# FX2LP.net
KiCad netlist of a schematic drawn in Altium Designer
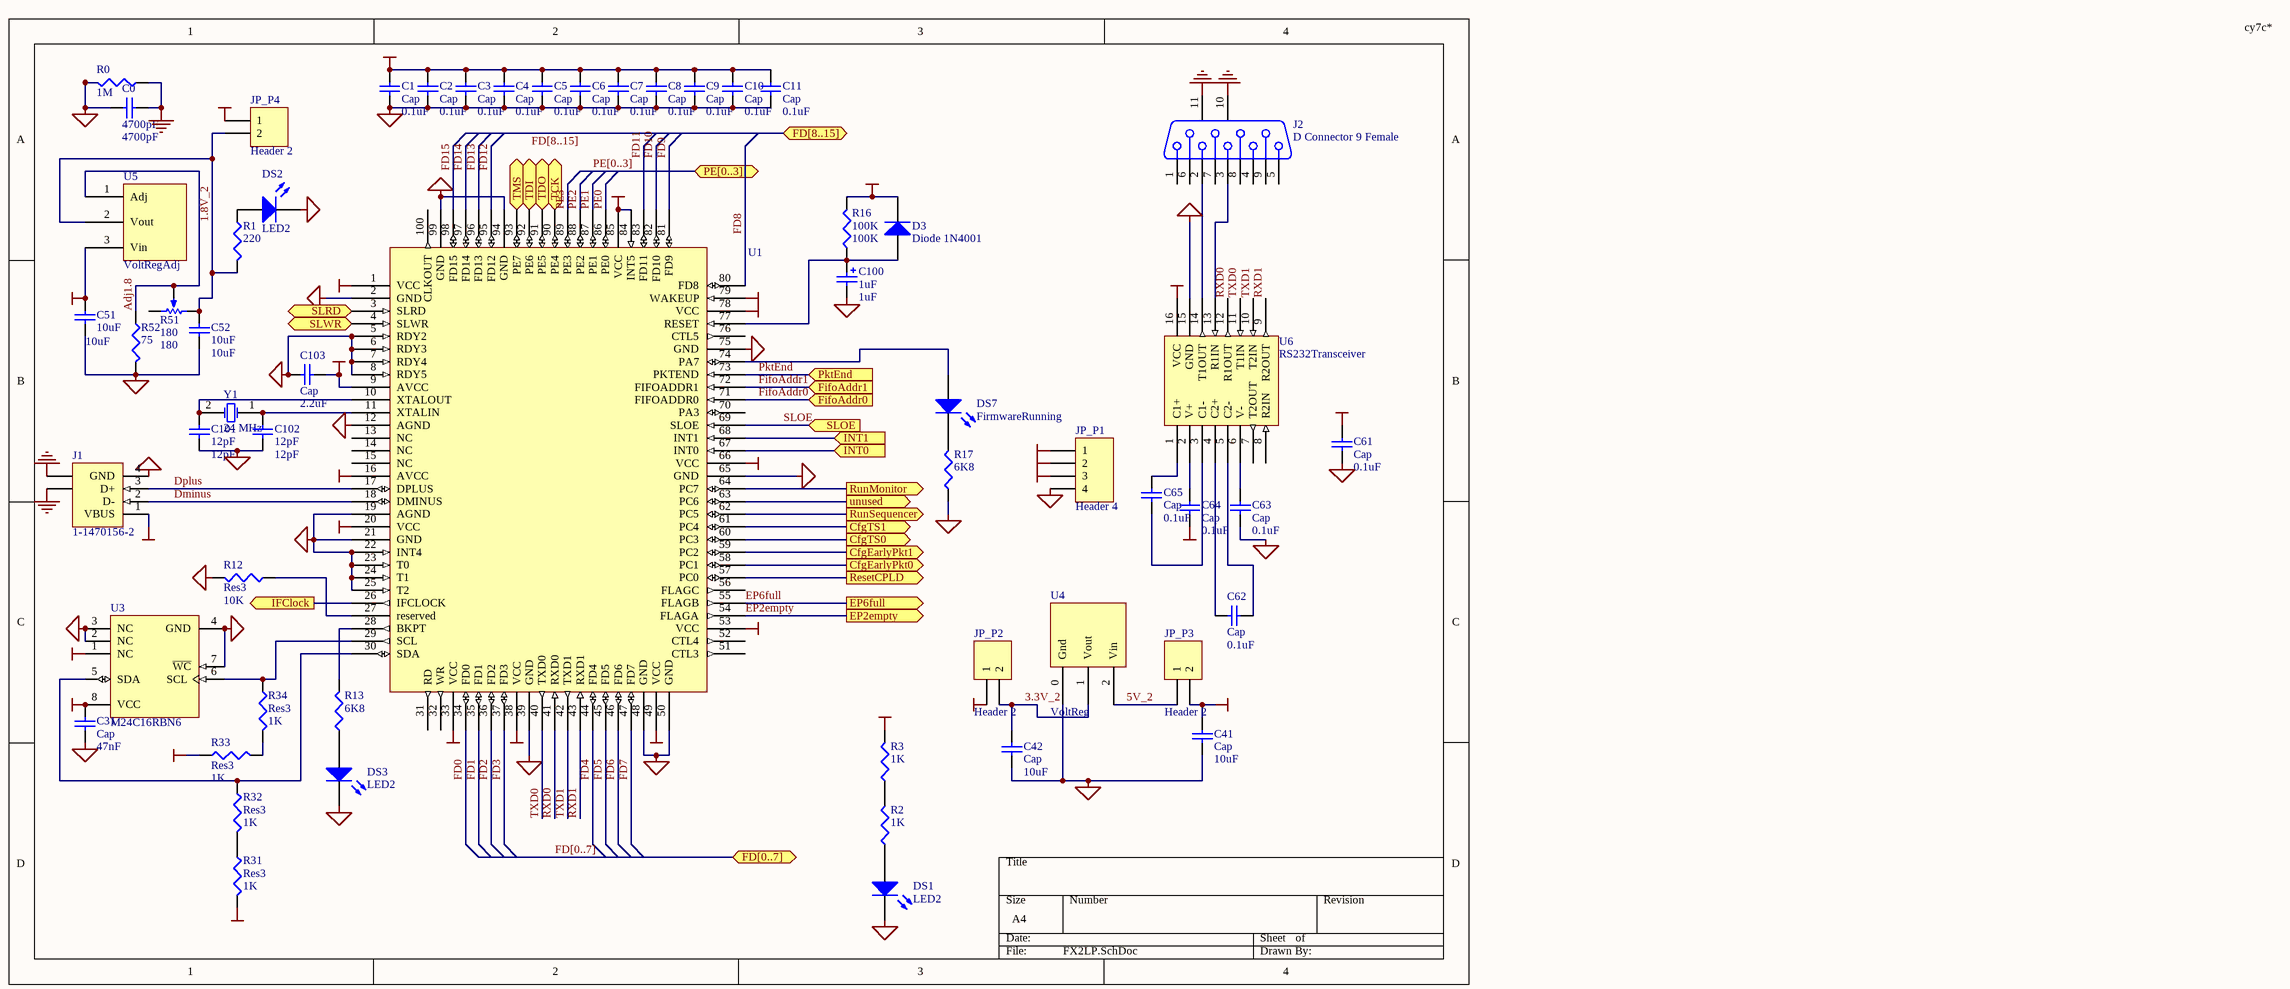
[diagram p0: FX2LP.SchDoc]

(export (version "E")
  (design (tool "Eeschema 10.0.6"))
  (components
    (comp (ref "C0")
      (value "4700pF")
      (footprint "CAP 10")
      (description "Capacitor")
      (fields (field (name "ALTIUM_VALUE") "4700pF") (field (name "PUBLISHER") "Altium Limited"))
      (libsource (lib "Miscellaneous Devices") (part "Cap"))
    )
    (comp (ref "C1")
      (value "Cap")
      (footprint "CAP 10")
      (description "Capacitor")
      (fields (field (name "ALTIUM_VALUE") "0.1uF") (field (name "PUBLISHER") "Altium Limited"))
      (libsource (lib "Miscellaneous Devices") (part "Cap"))
    )
    (comp (ref "C2")
      (value "Cap")
      (footprint "CAP 10")
      (description "Capacitor")
      (fields (field (name "ALTIUM_VALUE") "0.1uF") (field (name "PUBLISHER") "Altium Limited"))
      (libsource (lib "Miscellaneous Devices") (part "Cap"))
    )
    (comp (ref "C3")
      (value "Cap")
      (footprint "CAP 10")
      (description "Capacitor")
      (fields (field (name "ALTIUM_VALUE") "0.1uF") (field (name "PUBLISHER") "Altium Limited"))
      (libsource (lib "Miscellaneous Devices") (part "Cap"))
    )
    (comp (ref "C4")
      (value "Cap")
      (footprint "CAP 10")
      (description "Capacitor")
      (fields (field (name "ALTIUM_VALUE") "0.1uF") (field (name "PUBLISHER") "Altium Limited"))
      (libsource (lib "Miscellaneous Devices") (part "Cap"))
    )
    (comp (ref "C5")
      (value "Cap")
      (footprint "CAP 10")
      (description "Capacitor")
      (fields (field (name "ALTIUM_VALUE") "0.1uF") (field (name "PUBLISHER") "Altium Limited"))
      (libsource (lib "Miscellaneous Devices") (part "Cap"))
    )
    (comp (ref "C6")
      (value "Cap")
      (footprint "CAP 10")
      (description "Capacitor")
      (fields (field (name "ALTIUM_VALUE") "0.1uF") (field (name "PUBLISHER") "Altium Limited"))
      (libsource (lib "Miscellaneous Devices") (part "Cap"))
    )
    (comp (ref "C7")
      (value "Cap")
      (footprint "CAP 10")
      (description "Capacitor")
      (fields (field (name "ALTIUM_VALUE") "0.1uF") (field (name "PUBLISHER") "Altium Limited"))
      (libsource (lib "Miscellaneous Devices") (part "Cap"))
    )
    (comp (ref "C8")
      (value "Cap")
      (footprint "CAP 10")
      (description "Capacitor")
      (fields (field (name "ALTIUM_VALUE") "0.1uF") (field (name "PUBLISHER") "Altium Limited"))
      (libsource (lib "Miscellaneous Devices") (part "Cap"))
    )
    (comp (ref "C9")
      (value "Cap")
      (footprint "CAP 10")
      (description "Capacitor")
      (fields (field (name "ALTIUM_VALUE") "0.1uF") (field (name "PUBLISHER") "Altium Limited"))
      (libsource (lib "Miscellaneous Devices") (part "Cap"))
    )
    (comp (ref "C10")
      (value "Cap")
      (footprint "CAP 10")
      (description "Capacitor")
      (fields (field (name "ALTIUM_VALUE") "0.1uF") (field (name "PUBLISHER") "Altium Limited"))
      (libsource (lib "Miscellaneous Devices") (part "Cap"))
    )
    (comp (ref "C11")
      (value "Cap")
      (footprint "CAP 10")
      (description "Capacitor")
      (fields (field (name "ALTIUM_VALUE") "0.1uF") (field (name "PUBLISHER") "Altium Limited"))
      (libsource (lib "Miscellaneous Devices") (part "Cap"))
    )
    (comp (ref "C31")
      (value "Cap")
      (footprint "CAP 10")
      (description "Capacitor")
      (fields (field (name "ALTIUM_VALUE") "47nF") (field (name "PUBLISHER") "Altium Limited"))
      (libsource (lib "Miscellaneous Devices") (part "Cap"))
    )
    (comp (ref "C41")
      (value "Cap")
      (footprint "1206(2)")
      (description "Capacitor")
      (fields (field (name "ALTIUM_VALUE") "10uF") (field (name "PUBLISHER") "Altium Limited"))
      (libsource (lib "Miscellaneous Devices") (part "Cap"))
    )
    (comp (ref "C42")
      (value "Cap")
      (footprint "1206(2)")
      (description "Capacitor")
      (fields (field (name "ALTIUM_VALUE") "10uF") (field (name "PUBLISHER") "Altium Limited"))
      (libsource (lib "Miscellaneous Devices") (part "Cap"))
    )
    (comp (ref "C51")
      (value "10uF")
      (footprint "1206(2)")
      (description "Capacitor")
      (fields (field (name "ALTIUM_VALUE") "10uF") (field (name "PUBLISHER") "Altium Limited"))
      (libsource (lib "Miscellaneous Devices") (part "Cap"))
    )
    (comp (ref "C52")
      (value "10uF")
      (footprint "1206(2)")
      (description "Capacitor")
      (fields (field (name "ALTIUM_VALUE") "10uF") (field (name "PUBLISHER") "Altium Limited"))
      (libsource (lib "Miscellaneous Devices") (part "Cap"))
    )
    (comp (ref "C61")
      (value "Cap")
      (footprint "CAP 10")
      (description "Capacitor")
      (fields (field (name "ALTIUM_VALUE") "0.1uF") (field (name "PUBLISHER") "Altium Limited"))
      (libsource (lib "Miscellaneous Devices") (part "Cap"))
    )
    (comp (ref "C62")
      (value "Cap")
      (footprint "CAP 10")
      (description "Capacitor")
      (fields (field (name "ALTIUM_VALUE") "0.1uF") (field (name "PUBLISHER") "Altium Limited"))
      (libsource (lib "Miscellaneous Devices") (part "Cap"))
    )
    (comp (ref "C63")
      (value "Cap")
      (footprint "CAP 10")
      (description "Capacitor")
      (fields (field (name "ALTIUM_VALUE") "0.1uF") (field (name "PUBLISHER") "Altium Limited"))
      (libsource (lib "Miscellaneous Devices") (part "Cap"))
    )
    (comp (ref "C64")
      (value "Cap")
      (footprint "CAP 10")
      (description "Capacitor")
      (fields (field (name "ALTIUM_VALUE") "0.1uF") (field (name "PUBLISHER") "Altium Limited"))
      (libsource (lib "Miscellaneous Devices") (part "Cap"))
    )
    (comp (ref "C65")
      (value "Cap")
      (footprint "CAP 10")
      (description "Capacitor")
      (fields (field (name "ALTIUM_VALUE") "0.1uF") (field (name "PUBLISHER") "Altium Limited"))
      (libsource (lib "Miscellaneous Devices") (part "Cap"))
    )
    (comp (ref "C100")
      (value "1uF")
      (footprint "CAP 10")
      (description "Polarized Capacitor (Surface Mount)")
      (fields (field (name "ALTIUM_VALUE") "1uF") (field (name "PUBLISHER") "Altium Limited"))
      (libsource (lib "Miscellaneous Devices") (part "Cap Pol3"))
    )
    (comp (ref "C101")
      (value "12pF")
      (footprint "CAP 10")
      (description "Capacitor")
      (fields (field (name "ALTIUM_VALUE") "12pF") (field (name "PUBLISHER") "Altium Limited"))
      (libsource (lib "Miscellaneous Devices") (part "Cap"))
    )
    (comp (ref "C102")
      (value "12pF")
      (footprint "CAP 10")
      (description "Capacitor")
      (fields (field (name "ALTIUM_VALUE") "12pF") (field (name "PUBLISHER") "Altium Limited"))
      (libsource (lib "Miscellaneous Devices") (part "Cap"))
    )
    (comp (ref "C103")
      (value "Cap")
      (footprint "1206(2)")
      (description "Capacitor")
      (fields (field (name "ALTIUM_VALUE") "2.2uF") (field (name "PUBLISHER") "Altium Limited"))
      (libsource (lib "Miscellaneous Devices") (part "Cap"))
    )
    (comp (ref "D3")
      (value "Diode 1N4001")
      (footprint "DIO10.46-5.3x2.8")
      (description "1 Amp General Purpose Rectifier")
      (fields (field (name "PUBLISHER") "Altium Limited"))
      (libsource (lib "Miscellaneous Devices") (part "Diode 1N4001"))
    )
    (comp (ref "DS1")
      (value "LED2")
      (footprint "LED")
      (description "Typical RED, GREEN, YELLOW, AMBER GaAs LED")
      (fields (field (name "PUBLISHER") "Altium Limited"))
      (libsource (lib "Miscellaneous Devices") (part "LED2"))
    )
    (comp (ref "DS2")
      (value "LED2")
      (footprint "LED")
      (description "Typical RED, GREEN, YELLOW, AMBER GaAs LED")
      (fields (field (name "PUBLISHER") "Altium Limited"))
      (libsource (lib "Miscellaneous Devices") (part "LED2"))
    )
    (comp (ref "DS3")
      (value "LED2")
      (footprint "LED")
      (description "Typical RED, GREEN, YELLOW, AMBER GaAs LED")
      (fields (field (name "PUBLISHER") "Altium Limited"))
      (libsource (lib "Miscellaneous Devices") (part "LED2"))
    )
    (comp (ref "DS7")
      (value "FirmwareRunning")
      (footprint "LED")
      (description "Typical RED, GREEN, YELLOW, AMBER GaAs LED")
      (fields (field (name "PUBLISHER") "Altium Limited"))
      (libsource (lib "Miscellaneous Devices") (part "LED2"))
    )
    (comp (ref "J1")
      (value "1-1470156-2")
      (footprint "1-1470156")
      (description "USB 1.1, Right Angle, Thru-Hole, B Type, Receptacle, 4 Position, Black")
      (fields (field (name "PUBLISHER") "Altium Limited"))
      (libsource (lib "AMP Serial Bus USB") (part "1-1470156-2"))
    )
    (comp (ref "J2")
      (value "D Connector 9 Female")
      (footprint "DSUB1.385-2H9")
      (description "Receptacle Assembly, 9 Position, Right Angle")
      (fields (field (name "PUBLISHER") "Altium Limited"))
      (libsource (lib "Miscellaneous Connectors") (part "D Connector 9"))
    )
    (comp (ref "JP_P1")
      (value "Header 4")
      (footprint "HDR1X4")
      (description "Header, 4-Pin")
      (fields (field (name "PUBLISHER") "Altium Limited"))
      (libsource (lib "Miscellaneous Connectors") (part "Header 4"))
    )
    (comp (ref "JP_P2")
      (value "Header 2")
      (footprint "HDR1X2")
      (description "Header, 2-Pin")
      (fields (field (name "PUBLISHER") "Altium Limited"))
      (libsource (lib "Miscellaneous Connectors") (part "Header 2"))
    )
    (comp (ref "JP_P3")
      (value "Header 2")
      (footprint "SIP-2")
      (description "Header, 2-Pin")
      (fields (field (name "PUBLISHER") "Altium Limited"))
      (libsource (lib "Miscellaneous Connectors") (part "Header 2"))
    )
    (comp (ref "JP_P4")
      (value "Header 2")
      (footprint "SIP-2")
      (description "Header, 2-Pin")
      (fields (field (name "PUBLISHER") "Altium Limited"))
      (libsource (lib "") (part "Header 2_1"))
    )
    (comp (ref "R0")
      (value "1M")
      (footprint "C1608-0603")
      (description "Resistor")
      (fields (field (name "Comment") "Res3") (field (name "PUBLISHER") "Altium Limited"))
      (libsource (lib "Miscellaneous Devices") (part "Res3"))
    )
    (comp (ref "R1")
      (value "220")
      (footprint "C1608-0603")
      (description "Resistor")
      (fields (field (name "Comment") "Res3") (field (name "PUBLISHER") "Altium Limited"))
      (libsource (lib "Miscellaneous Devices") (part "Res3"))
    )
    (comp (ref "R2")
      (value "1K")
      (footprint "C1608-0603")
      (description "Resistor")
      (fields (field (name "Comment") "Res3") (field (name "PUBLISHER") "Altium Limited"))
      (libsource (lib "Miscellaneous Devices") (part "Res3"))
    )
    (comp (ref "R3")
      (value "1K")
      (footprint "C1608-0603")
      (description "Resistor")
      (fields (field (name "Comment") "Res3") (field (name "PUBLISHER") "Altium Limited"))
      (libsource (lib "Miscellaneous Devices") (part "Res3"))
    )
    (comp (ref "R12")
      (value "Res3")
      (footprint "C1608-0603")
      (description "Resistor")
      (fields (field (name "ALTIUM_VALUE") "10K") (field (name "PUBLISHER") "Altium Limited"))
      (libsource (lib "Miscellaneous Devices") (part "Res3"))
    )
    (comp (ref "R13")
      (value "6K8")
      (footprint "C1608-0603")
      (description "Resistor")
      (fields (field (name "Comment") "Res3") (field (name "PUBLISHER") "Altium Limited"))
      (libsource (lib "Miscellaneous Devices") (part "Res3"))
    )
    (comp (ref "R16")
      (value "100K")
      (footprint "C1608-0603")
      (description "Resistor")
      (fields (field (name "ALTIUM_VALUE") "100K") (field (name "PUBLISHER") "Altium Limited"))
      (libsource (lib "Miscellaneous Devices") (part "Res3"))
    )
    (comp (ref "R17")
      (value "6K8")
      (footprint "C1608-0603")
      (description "Resistor")
      (fields (field (name "Comment") "Res3") (field (name "PUBLISHER") "Altium Limited"))
      (libsource (lib "Miscellaneous Devices") (part "Res3"))
    )
    (comp (ref "R31")
      (value "Res3")
      (footprint "C1608-0603")
      (description "Resistor")
      (fields (field (name "ALTIUM_VALUE") "1K") (field (name "PUBLISHER") "Altium Limited"))
      (libsource (lib "Miscellaneous Devices") (part "Res3"))
    )
    (comp (ref "R32")
      (value "Res3")
      (footprint "C1608-0603")
      (description "Resistor")
      (fields (field (name "ALTIUM_VALUE") "1K") (field (name "PUBLISHER") "Altium Limited"))
      (libsource (lib "Miscellaneous Devices") (part "Res3"))
    )
    (comp (ref "R33")
      (value "Res3")
      (footprint "C1608-0603")
      (description "Resistor")
      (fields (field (name "ALTIUM_VALUE") "1K") (field (name "PUBLISHER") "Altium Limited"))
      (libsource (lib "Miscellaneous Devices") (part "Res3"))
    )
    (comp (ref "R34")
      (value "Res3")
      (footprint "C1608-0603")
      (description "Resistor")
      (fields (field (name "ALTIUM_VALUE") "1K") (field (name "PUBLISHER") "Altium Limited"))
      (libsource (lib "Miscellaneous Devices") (part "Res3"))
    )
    (comp (ref "R51")
      (value "180")
      (footprint "Pot")
      (description "Potentiometer")
      (fields (field (name "ALTIUM_VALUE") "180") (field (name "PUBLISHER") "Altium Limited"))
      (libsource (lib "Miscellaneous Devices") (part "RPot"))
    )
    (comp (ref "R52")
      (value "75")
      (footprint "1206(2)")
      (description "Resistor")
      (fields (field (name "Comment") "Res3") (field (name "PUBLISHER") "Altium Limited"))
      (libsource (lib "Miscellaneous Devices") (part "Res3"))
    )
    (comp (ref "U1")
      (value "FX2LP")
      (footprint "R-QFP14x20-G100/X.4N")
      (description "Cypress FX2LP 100 pin")
      (libsource (lib "FX2LP") (part "FX2LP"))
    )
    (comp (ref "U3")
      (value "M24C16RBN6")
      (footprint "PSDIP8A")
      (description "16Kbit Serial I²C Bus EEPROM")
      (fields (field (name "PUBLISHER") "Altium Limited"))
      (libsource (lib "ST Memory EEPROM Serial") (part "M24C16RBN6"))
    )
    (comp (ref "U4")
      (value "VoltReg")
      (footprint "TO-220")
      (description "5 to 3.3 volts regulator")
      (libsource (lib "FX2LP") (part "VoltReg"))
    )
    (comp (ref "U5") (value "VoltRegAdj") (footprint "TO-220") (libsource (lib "FX2LP") (part "VoltRegAdj")))
    (comp (ref "U6")
      (value "RS232Transceiver")
      (footprint "TSSO5x6-G16")
      (description "Analog Devices RS232 Transceiver")
      (libsource (lib "FX2LP") (part "RS232Transceiver"))
    )
    (comp (ref "Y1")
      (value "24 MHz")
      (footprint "Cristal")
      (description "Crystal Oscillator")
      (fields (field (name "PUBLISHER") "Altium Limited"))
      (libsource (lib "Miscellaneous Devices") (part "XTAL"))
    )
  )
  (nets
    (net (code "1") (name "/5V_2") (class "Default")
      (node (ref "JP_P3") (pin "1") (pinfunction "1_1") (pintype "passive"))
      (node (ref "U4") (pin "2") (pinfunction "Vin_2") (pintype "power_in"))
    )
    (net (code "2") (name "/Adj1.8") (class "Default")
      (node (ref "R51") (pin "3") (pinfunction "TAP_3") (pintype "passive"))
      (node (ref "R52") (pin "1") (pinfunction "1_1") (pintype "passive"))
      (node (ref "U5") (pin "1") (pinfunction "Adj_1") (pintype "power_in"))
    )
    (net (code "3") (name "/CfgEarlyPkt0") (class "Default")
      (node (ref "U1") (pin "58") (pinfunction "PC1_58") (pintype "bidirectional"))
    )
    (net (code "4") (name "/CfgEarlyPkt1") (class "Default")
      (node (ref "U1") (pin "59") (pinfunction "PC2_59") (pintype "bidirectional"))
    )
    (net (code "5") (name "/CfgTS0") (class "Default")
      (node (ref "U1") (pin "60") (pinfunction "PC3_60") (pintype "bidirectional"))
    )
    (net (code "6") (name "/CfgTS1") (class "Default")
      (node (ref "U1") (pin "61") (pinfunction "PC4_61") (pintype "bidirectional"))
    )
    (net (code "7") (name "/Dminus") (class "Default")
      (node (ref "J1") (pin "2") (pinfunction "D-_2") (pintype "input"))
      (node (ref "U1") (pin "18") (pinfunction "DMINUS_18") (pintype "bidirectional"))
    )
    (net (code "8") (name "/Dplus") (class "Default")
      (node (ref "J1") (pin "3") (pinfunction "D+_3") (pintype "input"))
      (node (ref "U1") (pin "17") (pinfunction "DPLUS_17") (pintype "bidirectional"))
    )
    (net (code "9") (name "/EP2empty") (class "Default")
      (node (ref "U1") (pin "54") (pinfunction "FLAGA_54") (pintype "output"))
    )
    (net (code "10") (name "/EP6full") (class "Default")
      (node (ref "U1") (pin "55") (pinfunction "FLAGB_55") (pintype "output"))
    )
    (net (code "11") (name "/FD0") (class "Default")
      (node (ref "U1") (pin "34") (pinfunction "FD0_34") (pintype "bidirectional"))
    )
    (net (code "12") (name "/FD1") (class "Default")
      (node (ref "U1") (pin "35") (pinfunction "FD1_35") (pintype "bidirectional"))
    )
    (net (code "13") (name "/FD2") (class "Default")
      (node (ref "U1") (pin "36") (pinfunction "FD2_36") (pintype "bidirectional"))
    )
    (net (code "14") (name "/FD3") (class "Default")
      (node (ref "U1") (pin "37") (pinfunction "FD3_37") (pintype "bidirectional"))
    )
    (net (code "15") (name "/FD4") (class "Default")
      (node (ref "U1") (pin "44") (pinfunction "FD4_44") (pintype "bidirectional"))
    )
    (net (code "16") (name "/FD5") (class "Default")
      (node (ref "U1") (pin "45") (pinfunction "FD5_45") (pintype "bidirectional"))
    )
    (net (code "17") (name "/FD6") (class "Default")
      (node (ref "U1") (pin "46") (pinfunction "FD6_46") (pintype "bidirectional"))
    )
    (net (code "18") (name "/FD7") (class "Default")
      (node (ref "U1") (pin "47") (pinfunction "FD7_47") (pintype "bidirectional"))
    )
    (net (code "19") (name "/FD8") (class "Default")
      (node (ref "U1") (pin "80") (pinfunction "FD8_80") (pintype "bidirectional"))
    )
    (net (code "20") (name "/FD9") (class "Default")
      (node (ref "U1") (pin "81") (pinfunction "FD9_81") (pintype "bidirectional"))
    )
    (net (code "21") (name "/FD10") (class "Default")
      (node (ref "U1") (pin "82") (pinfunction "FD10_82") (pintype "bidirectional"))
    )
    (net (code "22") (name "/FD11") (class "Default")
      (node (ref "U1") (pin "83") (pinfunction "FD11_83") (pintype "bidirectional"))
    )
    (net (code "23") (name "/FD12") (class "Default")
      (node (ref "U1") (pin "95") (pinfunction "FD12_95") (pintype "bidirectional"))
    )
    (net (code "24") (name "/FD13") (class "Default")
      (node (ref "U1") (pin "96") (pinfunction "FD13_96") (pintype "bidirectional"))
    )
    (net (code "25") (name "/FD14") (class "Default")
      (node (ref "U1") (pin "97") (pinfunction "FD14_97") (pintype "bidirectional"))
    )
    (net (code "26") (name "/FD15") (class "Default")
      (node (ref "U1") (pin "98") (pinfunction "FD15_98") (pintype "bidirectional"))
    )
    (net (code "29") (name "/FifoAddr0") (class "Default")
      (node (ref "U1") (pin "71") (pinfunction "FIFOADDR0_71") (pintype "input"))
    )
    (net (code "30") (name "/FifoAddr1") (class "Default")
      (node (ref "U1") (pin "72") (pinfunction "FIFOADDR1_72") (pintype "input"))
    )
    (net (code "31") (name "/IFClock") (class "Default")
      (node (ref "U1") (pin "26") (pinfunction "IFCLOCK_26") (pintype "output"))
    )
    (net (code "32") (name "/INT0") (class "Default")
      (node (ref "U1") (pin "67") (pinfunction "INT0_67") (pintype "input"))
    )
    (net (code "33") (name "/INT1") (class "Default")
      (node (ref "U1") (pin "68") (pinfunction "INT1_68") (pintype "input"))
    )
    (net (code "34") (name "/PE0") (class "Default")
      (node (ref "U1") (pin "86") (pinfunction "PE0_86") (pintype "bidirectional"))
    )
    (net (code "35") (name "/PE1") (class "Default")
      (node (ref "U1") (pin "87") (pinfunction "PE1_87") (pintype "bidirectional"))
    )
    (net (code "36") (name "/PE2") (class "Default")
      (node (ref "U1") (pin "88") (pinfunction "PE2_88") (pintype "bidirectional"))
    )
    (net (code "37") (name "/PE3") (class "Default")
      (node (ref "U1") (pin "89") (pinfunction "PE3_89") (pintype "bidirectional"))
    )
    (net (code "39") (name "/PktEnd") (class "Default")
      (node (ref "U1") (pin "73") (pinfunction "PKTEND_73") (pintype "input"))
    )
    (net (code "40") (name "/RXD0") (class "Default")
      (node (ref "U1") (pin "41") (pinfunction "RXD0_41") (pintype "input"))
      (node (ref "U6") (pin "12") (pinfunction "R1OUT_12") (pintype "output"))
    )
    (net (code "41") (name "/RXD1") (class "Default")
      (node (ref "U1") (pin "43") (pinfunction "RXD1_43") (pintype "input"))
      (node (ref "U6") (pin "9") (pinfunction "R2OUT_9") (pintype "output"))
    )
    (net (code "42") (name "/ResetCPLD") (class "Default")
      (node (ref "U1") (pin "57") (pinfunction "PC0_57") (pintype "bidirectional"))
    )
    (net (code "43") (name "/RunMonitor") (class "Default")
      (node (ref "U1") (pin "64") (pinfunction "PC7_64") (pintype "bidirectional"))
    )
    (net (code "44") (name "/RunSequencer") (class "Default")
      (node (ref "U1") (pin "62") (pinfunction "PC5_62") (pintype "bidirectional"))
    )
    (net (code "45") (name "/SLOE") (class "Default")
      (node (ref "U1") (pin "69") (pinfunction "SLOE_69") (pintype "input"))
    )
    (net (code "46") (name "/SLRD") (class "Default")
      (node (ref "U1") (pin "3") (pinfunction "SLRD_3") (pintype "input"))
    )
    (net (code "47") (name "/SLWR") (class "Default")
      (node (ref "U1") (pin "4") (pinfunction "SLWR_4") (pintype "input"))
    )
    (net (code "48") (name "/TCK") (class "Default")
      (node (ref "U1") (pin "90") (pinfunction "PE4_90") (pintype "bidirectional"))
    )
    (net (code "49") (name "/TDI") (class "Default")
      (node (ref "U1") (pin "92") (pinfunction "PE6_92") (pintype "bidirectional"))
    )
    (net (code "50") (name "/TDO") (class "Default")
      (node (ref "U1") (pin "91") (pinfunction "PE5_91") (pintype "bidirectional"))
    )
    (net (code "51") (name "/TMS") (class "Default")
      (node (ref "U1") (pin "93") (pinfunction "PE7_93") (pintype "bidirectional"))
    )
    (net (code "52") (name "/TXD0") (class "Default")
      (node (ref "U1") (pin "40") (pinfunction "TXD0_40") (pintype "output"))
      (node (ref "U6") (pin "11") (pinfunction "T1IN_11") (pintype "input"))
    )
    (net (code "53") (name "/TXD1") (class "Default")
      (node (ref "U1") (pin "42") (pinfunction "TXD1_42") (pintype "output"))
      (node (ref "U6") (pin "10") (pinfunction "T2IN_10") (pintype "input"))
    )
    (net (code "54") (name "/unused") (class "Default")
      (node (ref "U1") (pin "63") (pinfunction "PC6_63") (pintype "bidirectional"))
    )
    (net (code "55") (name "1.8V") (class "Default")
      (node (ref "JP_P4") (pin "1") (pinfunction "1_1") (pintype "passive"))
    )
    (net (code "56") (name "1.8V_2") (class "Default")
      (node (ref "C52") (pin "1") (pinfunction "1_1") (pintype "passive"))
      (node (ref "JP_P1") (pin "3") (pinfunction "3_3") (pintype "passive"))
      (node (ref "JP_P4") (pin "2") (pinfunction "2_2") (pintype "passive"))
      (node (ref "R1") (pin "2") (pinfunction "2_2") (pintype "passive"))
      (node (ref "R51") (pin "1") (pinfunction "TOP_1") (pintype "passive"))
      (node (ref "U5") (pin "2") (pinfunction "Vout_2") (pintype "power_in"))
    )
    (net (code "57") (name "3.3V") (class "Default")
      (node (ref "C1") (pin "2") (pinfunction "2_2") (pintype "passive"))
      (node (ref "C10") (pin "2") (pinfunction "2_2") (pintype "passive"))
      (node (ref "C103") (pin "1") (pinfunction "1_1") (pintype "passive"))
      (node (ref "C11") (pin "2") (pinfunction "2_2") (pintype "passive"))
      (node (ref "C2") (pin "2") (pinfunction "2_2") (pintype "passive"))
      (node (ref "C3") (pin "2") (pinfunction "2_2") (pintype "passive"))
      (node (ref "C31") (pin "2") (pinfunction "2_2") (pintype "passive"))
      (node (ref "C4") (pin "2") (pinfunction "2_2") (pintype "passive"))
      (node (ref "C5") (pin "2") (pinfunction "2_2") (pintype "passive"))
      (node (ref "C51") (pin "1") (pinfunction "1_1") (pintype "passive"))
      (node (ref "C6") (pin "2") (pinfunction "2_2") (pintype "passive"))
      (node (ref "C61") (pin "2") (pinfunction "2_2") (pintype "passive"))
      (node (ref "C64") (pin "1") (pinfunction "1_1") (pintype "passive"))
      (node (ref "C7") (pin "2") (pinfunction "2_2") (pintype "passive"))
      (node (ref "C8") (pin "2") (pinfunction "2_2") (pintype "passive"))
      (node (ref "C9") (pin "2") (pinfunction "2_2") (pintype "passive"))
      (node (ref "D3") (pin "2") (pinfunction "K_2") (pintype "passive"))
      (node (ref "JP_P2") (pin "1") (pinfunction "1_1") (pintype "passive"))
      (node (ref "R16") (pin "2") (pinfunction "2_2") (pintype "passive"))
      (node (ref "R31") (pin "2") (pinfunction "2_2") (pintype "passive"))
      (node (ref "R33") (pin "1") (pinfunction "1_1") (pintype "passive"))
      (node (ref "U1") (pin "1") (pinfunction "VCC_1") (pintype "power_in"))
      (node (ref "U1") (pin "16") (pinfunction "AVCC_16") (pintype "power_in"))
      (node (ref "U1") (pin "20") (pinfunction "VCC_20") (pintype "power_in"))
      (node (ref "U1") (pin "33") (pinfunction "VCC_33") (pintype "power_in"))
      (node (ref "U1") (pin "38") (pinfunction "VCC_38") (pintype "power_in"))
      (node (ref "U1") (pin "49") (pinfunction "VCC_49") (pintype "power_in"))
      (node (ref "U1") (pin "53") (pinfunction "VCC_53") (pintype "power_in"))
      (node (ref "U1") (pin "66") (pinfunction "VCC_66") (pintype "power_in"))
      (node (ref "U1") (pin "78") (pinfunction "VCC_78") (pintype "power_in"))
      (node (ref "U1") (pin "79") (pinfunction "WAKEUP_79") (pintype "input"))
      (node (ref "U1") (pin "84") (pinfunction "INT5_84") (pintype "input"))
      (node (ref "U1") (pin "85") (pinfunction "VCC_85") (pintype "power_in"))
      (node (ref "U1") (pin "9") (pinfunction "AVCC_9") (pintype "passive"))
      (node (ref "U3") (pin "1") (pinfunction "NC_1") (pintype "passive"))
      (node (ref "U3") (pin "8") (pinfunction "VCC_8") (pintype "power_in"))
      (node (ref "U5") (pin "3") (pinfunction "Vin_3") (pintype "power_in"))
      (node (ref "U6") (pin "16") (pinfunction "VCC_16") (pintype "power_in"))
    )
    (net (code "58") (name "3.3V_2") (class "Default")
      (node (ref "C42") (pin "1") (pinfunction "1_1") (pintype "passive"))
      (node (ref "JP_P1") (pin "2") (pinfunction "2_2") (pintype "passive"))
      (node (ref "JP_P2") (pin "2") (pinfunction "2_2") (pintype "passive"))
      (node (ref "R3") (pin "2") (pinfunction "2_2") (pintype "passive"))
      (node (ref "U4") (pin "1") (pinfunction "Vout_1") (pintype "power_in"))
    )
    (net (code "59") (name "5V") (class "Default")
      (node (ref "C41") (pin "1") (pinfunction "1_1") (pintype "passive"))
      (node (ref "J1") (pin "1") (pinfunction "VBUS_1") (pintype "power_in"))
      (node (ref "JP_P1") (pin "1") (pinfunction "1_1") (pintype "passive"))
      (node (ref "JP_P3") (pin "2") (pinfunction "2_2") (pintype "passive"))
    )
    (net (code "60") (name "AGND") (class "Default")
      (node (ref "C0") (pin "2") (pinfunction "2_2") (pintype "passive"))
      (node (ref "J1") (pin "5") (pinfunction "SHLD_5") (pintype "passive"))
      (node (ref "J1") (pin "6") (pinfunction "SHLD_6") (pintype "passive"))
      (node (ref "J2") (pin "10") (pinfunction "MH1_10") (pintype "passive"))
      (node (ref "J2") (pin "11") (pinfunction "MH2_11") (pintype "passive"))
      (node (ref "R0") (pin "1") (pinfunction "1_1") (pintype "passive"))
    )
    (net (code "61") (name "GND") (class "Default")
      (node (ref "C0") (pin "1") (pinfunction "1_1") (pintype "passive"))
      (node (ref "C1") (pin "1") (pinfunction "1_1") (pintype "passive"))
      (node (ref "C10") (pin "1") (pinfunction "1_1") (pintype "passive"))
      (node (ref "C100") (pin "2") (pinfunction "2_2") (pintype "passive"))
      (node (ref "C101") (pin "2") (pinfunction "2_2") (pintype "passive"))
      (node (ref "C102") (pin "2") (pinfunction "2_2") (pintype "passive"))
      (node (ref "C103") (pin "2") (pinfunction "2_2") (pintype "passive"))
      (node (ref "C11") (pin "1") (pinfunction "1_1") (pintype "passive"))
      (node (ref "C2") (pin "1") (pinfunction "1_1") (pintype "passive"))
      (node (ref "C3") (pin "1") (pinfunction "1_1") (pintype "passive"))
      (node (ref "C31") (pin "1") (pinfunction "1_1") (pintype "passive"))
      (node (ref "C4") (pin "1") (pinfunction "1_1") (pintype "passive"))
      (node (ref "C41") (pin "2") (pinfunction "2_2") (pintype "passive"))
      (node (ref "C42") (pin "2") (pinfunction "2_2") (pintype "passive"))
      (node (ref "C5") (pin "1") (pinfunction "1_1") (pintype "passive"))
      (node (ref "C51") (pin "2") (pinfunction "2_2") (pintype "passive"))
      (node (ref "C52") (pin "2") (pinfunction "2_2") (pintype "passive"))
      (node (ref "C6") (pin "1") (pinfunction "1_1") (pintype "passive"))
      (node (ref "C61") (pin "1") (pinfunction "1_1") (pintype "passive"))
      (node (ref "C63") (pin "1") (pinfunction "1_1") (pintype "passive"))
      (node (ref "C7") (pin "1") (pinfunction "1_1") (pintype "passive"))
      (node (ref "C8") (pin "1") (pinfunction "1_1") (pintype "passive"))
      (node (ref "C9") (pin "1") (pinfunction "1_1") (pintype "passive"))
      (node (ref "DS1") (pin "2") (pinfunction "K_2") (pintype "passive"))
      (node (ref "DS2") (pin "2") (pinfunction "K_2") (pintype "passive"))
      (node (ref "DS3") (pin "2") (pinfunction "K_2") (pintype "passive"))
      (node (ref "J1") (pin "4") (pinfunction "GND_4") (pintype "power_in"))
      (node (ref "JP_P1") (pin "4") (pinfunction "4_4") (pintype "passive"))
      (node (ref "R0") (pin "2") (pinfunction "2_2") (pintype "passive"))
      (node (ref "R12") (pin "2") (pinfunction "2_2") (pintype "passive"))
      (node (ref "R17") (pin "1") (pinfunction "1_1") (pintype "passive"))
      (node (ref "R52") (pin "2") (pinfunction "2_2") (pintype "passive"))
      (node (ref "U1") (pin "12") (pinfunction "AGND_12") (pintype "power_in"))
      (node (ref "U1") (pin "19") (pinfunction "AGND_19") (pintype "power_in"))
      (node (ref "U1") (pin "2") (pinfunction "GND_2") (pintype "power_in"))
      (node (ref "U1") (pin "21") (pinfunction "GND_21") (pintype "power_in"))
      (node (ref "U1") (pin "22") (pinfunction "INT4_22") (pintype "input"))
      (node (ref "U1") (pin "23") (pinfunction "T0_23") (pintype "input"))
      (node (ref "U1") (pin "24") (pinfunction "T1_24") (pintype "input"))
      (node (ref "U1") (pin "25") (pinfunction "T2_25") (pintype "input"))
      (node (ref "U1") (pin "39") (pinfunction "GND_39") (pintype "power_in"))
      (node (ref "U1") (pin "48") (pinfunction "GND_48") (pintype "power_in"))
      (node (ref "U1") (pin "5") (pinfunction "RDY2_5") (pintype "input"))
      (node (ref "U1") (pin "50") (pinfunction "GND_50") (pintype "power_in"))
      (node (ref "U1") (pin "6") (pinfunction "RDY3_6") (pintype "input"))
      (node (ref "U1") (pin "65") (pinfunction "GND_65") (pintype "power_in"))
      (node (ref "U1") (pin "7") (pinfunction "RDY4_7") (pintype "input"))
      (node (ref "U1") (pin "75") (pinfunction "GND_75") (pintype "power_in"))
      (node (ref "U1") (pin "8") (pinfunction "RDY5_8") (pintype "input"))
      (node (ref "U1") (pin "94") (pinfunction "GND_94") (pintype "power_in"))
      (node (ref "U1") (pin "99") (pinfunction "GND_99") (pintype "power_in"))
      (node (ref "U3") (pin "2") (pinfunction "NC_2") (pintype "passive"))
      (node (ref "U3") (pin "3") (pinfunction "NC_3") (pintype "passive"))
      (node (ref "U3") (pin "4") (pinfunction "GND_4") (pintype "power_in"))
      (node (ref "U3") (pin "7") (pinfunction "~{WC}_7") (pintype "input"))
      (node (ref "U4") (pin "0") (pinfunction "Gnd_0") (pintype "power_in"))
      (node (ref "U6") (pin "15") (pinfunction "GND_15") (pintype "power_in"))
    )
    (net (code "62") (name "Net-(D3-A)") (class "Default")
      (node (ref "C100") (pin "1") (pinfunction "1_1") (pintype "passive"))
      (node (ref "D3") (pin "1") (pinfunction "A_1") (pintype "passive"))
      (node (ref "R16") (pin "1") (pinfunction "1_1") (pintype "passive"))
      (node (ref "U1") (pin "77") (pinfunction "RESET_77") (pintype "input"))
    )
    (net (code "63") (name "Net-(DS1-A)") (class "Default")
      (node (ref "DS1") (pin "1") (pinfunction "A_1") (pintype "passive"))
      (node (ref "R2") (pin "1") (pinfunction "1_1") (pintype "passive"))
    )
    (net (code "64") (name "Net-(DS2-A)") (class "Default")
      (node (ref "DS2") (pin "1") (pinfunction "A_1") (pintype "passive"))
      (node (ref "R1") (pin "1") (pinfunction "1_1") (pintype "passive"))
    )
    (net (code "65") (name "Net-(DS3-A)") (class "Default")
      (node (ref "DS3") (pin "1") (pinfunction "A_1") (pintype "passive"))
      (node (ref "R13") (pin "1") (pinfunction "1_1") (pintype "passive"))
    )
    (net (code "66") (name "Net-(DS7-A)") (class "Default")
      (node (ref "DS7") (pin "1") (pinfunction "A_1") (pintype "passive"))
      (node (ref "U1") (pin "74") (pinfunction "PA7_74") (pintype "bidirectional"))
    )
    (net (code "67") (name "Net-(DS7-K)") (class "Default")
      (node (ref "DS7") (pin "2") (pinfunction "K_2") (pintype "passive"))
      (node (ref "R17") (pin "2") (pinfunction "2_2") (pintype "passive"))
    )
    (net (code "68") (name "Net-(R2-Pad2)") (class "Default")
      (node (ref "R2") (pin "2") (pinfunction "2_2") (pintype "passive"))
      (node (ref "R3") (pin "1") (pinfunction "1_1") (pintype "passive"))
    )
    (net (code "69") (name "Net-(R31-Pad1)") (class "Default")
      (node (ref "R31") (pin "1") (pinfunction "1_1") (pintype "passive"))
      (node (ref "R32") (pin "2") (pinfunction "2_2") (pintype "passive"))
    )
    (net (code "70") (name "Net-(R33-Pad2)") (class "Default")
      (node (ref "R33") (pin "2") (pinfunction "2_2") (pintype "passive"))
      (node (ref "R34") (pin "2") (pinfunction "2_2") (pintype "passive"))
    )
    (net (code "71") (name "Net-(U1-BKPT)") (class "Default")
      (node (ref "R13") (pin "2") (pinfunction "2_2") (pintype "passive"))
      (node (ref "U1") (pin "28") (pinfunction "BKPT_28") (pintype "output"))
    )
    (net (code "72") (name "Net-(U1-SCL)") (class "Default")
      (node (ref "R34") (pin "1") (pinfunction "1_1") (pintype "passive"))
      (node (ref "U1") (pin "29") (pinfunction "SCL_29") (pintype "output"))
      (node (ref "U3") (pin "6") (pinfunction "SCL_6") (pintype "input"))
    )
    (net (code "73") (name "Net-(U1-SDA)") (class "Default")
      (node (ref "R32") (pin "1") (pinfunction "1_1") (pintype "passive"))
      (node (ref "U1") (pin "30") (pinfunction "SDA_30") (pintype "bidirectional"))
      (node (ref "U3") (pin "5") (pinfunction "SDA_5") (pintype "bidirectional"))
    )
    (net (code "74") (name "Net-(U1-XTALIN)") (class "Default")
      (node (ref "C102") (pin "1") (pinfunction "1_1") (pintype "passive"))
      (node (ref "U1") (pin "11") (pinfunction "XTALIN_11") (pintype "passive"))
      (node (ref "Y1") (pin "1") (pinfunction "OSC1_1") (pintype "passive"))
    )
    (net (code "75") (name "Net-(U1-XTALOUT)") (class "Default")
      (node (ref "C101") (pin "1") (pinfunction "1_1") (pintype "passive"))
      (node (ref "U1") (pin "10") (pinfunction "XTALOUT_10") (pintype "passive"))
      (node (ref "Y1") (pin "2") (pinfunction "OSC2_2") (pintype "passive"))
    )
    (net (code "76") (name "Net-(U1-reserved)") (class "Default")
      (node (ref "R12") (pin "1") (pinfunction "1_1") (pintype "passive"))
      (node (ref "U1") (pin "27") (pinfunction "reserved_27") (pintype "passive"))
    )
    (net (code "77") (name "Net-(U6-C1+)") (class "Default")
      (node (ref "C65") (pin "2") (pinfunction "2_2") (pintype "passive"))
      (node (ref "U6") (pin "1") (pinfunction "C1+_1") (pintype "power_in"))
    )
    (net (code "78") (name "Net-(U6-C1-)") (class "Default")
      (node (ref "C65") (pin "1") (pinfunction "1_1") (pintype "passive"))
      (node (ref "U6") (pin "3") (pinfunction "C1-_3") (pintype "power_in"))
    )
    (net (code "79") (name "Net-(U6-C2+)") (class "Default")
      (node (ref "C62") (pin "2") (pinfunction "2_2") (pintype "passive"))
      (node (ref "U6") (pin "4") (pinfunction "C2+_4") (pintype "power_in"))
    )
    (net (code "80") (name "Net-(U6-C2-)") (class "Default")
      (node (ref "C62") (pin "1") (pinfunction "1_1") (pintype "passive"))
      (node (ref "U6") (pin "5") (pinfunction "C2-_5") (pintype "power_in"))
    )
    (net (code "81") (name "Net-(U6-R1IN)") (class "Default")
      (node (ref "J2") (pin "3") (pinfunction "3_3") (pintype "passive"))
      (node (ref "U6") (pin "13") (pinfunction "R1IN_13") (pintype "input"))
    )
    (net (code "82") (name "Net-(U6-T1OUT)") (class "Default")
      (node (ref "J2") (pin "2") (pinfunction "2_2") (pintype "passive"))
      (node (ref "U6") (pin "14") (pinfunction "T1OUT_14") (pintype "output"))
    )
    (net (code "83") (name "Net-(U6-V+)") (class "Default")
      (node (ref "C64") (pin "2") (pinfunction "2_2") (pintype "passive"))
      (node (ref "U6") (pin "2") (pinfunction "V+_2") (pintype "power_in"))
    )
    (net (code "84") (name "Net-(U6-V-)") (class "Default")
      (node (ref "C63") (pin "2") (pinfunction "2_2") (pintype "passive"))
      (node (ref "U6") (pin "6") (pinfunction "V-_6") (pintype "power_in"))
    )
    (net (code "85") (name "unconnected-(J2-Pad1)") (class "Default")
      (node (ref "J2") (pin "1") (pinfunction "1_1") (pintype "passive"))
    )
    (net (code "86") (name "unconnected-(J2-Pad4)") (class "Default")
      (node (ref "J2") (pin "4") (pinfunction "4_4") (pintype "passive"))
    )
    (net (code "87") (name "unconnected-(J2-Pad5)") (class "Default")
      (node (ref "J2") (pin "5") (pinfunction "5_5") (pintype "passive"))
    )
    (net (code "88") (name "unconnected-(J2-Pad6)") (class "Default")
      (node (ref "J2") (pin "6") (pinfunction "6_6") (pintype "passive"))
    )
    (net (code "89") (name "unconnected-(J2-Pad7)") (class "Default")
      (node (ref "J2") (pin "7") (pinfunction "7_7") (pintype "passive"))
    )
    (net (code "90") (name "unconnected-(J2-Pad8)") (class "Default")
      (node (ref "J2") (pin "8") (pinfunction "8_8") (pintype "passive"))
    )
    (net (code "91") (name "unconnected-(J2-Pad9)") (class "Default")
      (node (ref "J2") (pin "9") (pinfunction "9_9") (pintype "passive"))
    )
    (net (code "92") (name "unconnected-(R51-BOT-Pad2)") (class "Default")
      (node (ref "R51") (pin "2") (pinfunction "BOT_2") (pintype "passive"))
    )
    (net (code "93") (name "unconnected-(U1-CLKOUT-Pad100)") (class "Default")
      (node (ref "U1") (pin "100") (pinfunction "CLKOUT_100") (pintype "output"))
    )
    (net (code "94") (name "unconnected-(U1-CTL3-Pad51)") (class "Default")
      (node (ref "U1") (pin "51") (pinfunction "CTL3_51") (pintype "output"))
    )
    (net (code "95") (name "unconnected-(U1-CTL4-Pad52)") (class "Default")
      (node (ref "U1") (pin "52") (pinfunction "CTL4_52") (pintype "output"))
    )
    (net (code "96") (name "unconnected-(U1-CTL5-Pad76)") (class "Default")
      (node (ref "U1") (pin "76") (pinfunction "CTL5_76") (pintype "output"))
    )
    (net (code "97") (name "unconnected-(U1-FLAGC-Pad56)") (class "Default")
      (node (ref "U1") (pin "56") (pinfunction "FLAGC_56") (pintype "output"))
    )
    (net (code "98") (name "unconnected-(U1-NC-Pad13)") (class "Default")
      (node (ref "U1") (pin "13") (pinfunction "NC_13") (pintype "passive"))
    )
    (net (code "99") (name "unconnected-(U1-NC-Pad14)") (class "Default")
      (node (ref "U1") (pin "14") (pinfunction "NC_14") (pintype "passive"))
    )
    (net (code "100") (name "unconnected-(U1-NC-Pad15)") (class "Default")
      (node (ref "U1") (pin "15") (pinfunction "NC_15") (pintype "passive"))
    )
    (net (code "101") (name "unconnected-(U1-PA3-Pad70)") (class "Default")
      (node (ref "U1") (pin "70") (pinfunction "PA3_70") (pintype "bidirectional"))
    )
    (net (code "102") (name "unconnected-(U1-RD-Pad31)") (class "Default")
      (node (ref "U1") (pin "31") (pinfunction "RD_31") (pintype "output"))
    )
    (net (code "103") (name "unconnected-(U1-WR-Pad32)") (class "Default")
      (node (ref "U1") (pin "32") (pinfunction "WR_32") (pintype "output"))
    )
    (net (code "104") (name "unconnected-(U6-R2IN-Pad8)") (class "Default")
      (node (ref "U6") (pin "8") (pinfunction "R2IN_8") (pintype "input"))
    )
    (net (code "105") (name "unconnected-(U6-T2OUT-Pad7)") (class "Default")
      (node (ref "U6") (pin "7") (pinfunction "T2OUT_7") (pintype "output"))
    )
  )
)
